# feedback.net
KiCad netlist of a schematic drawn in EAGLE
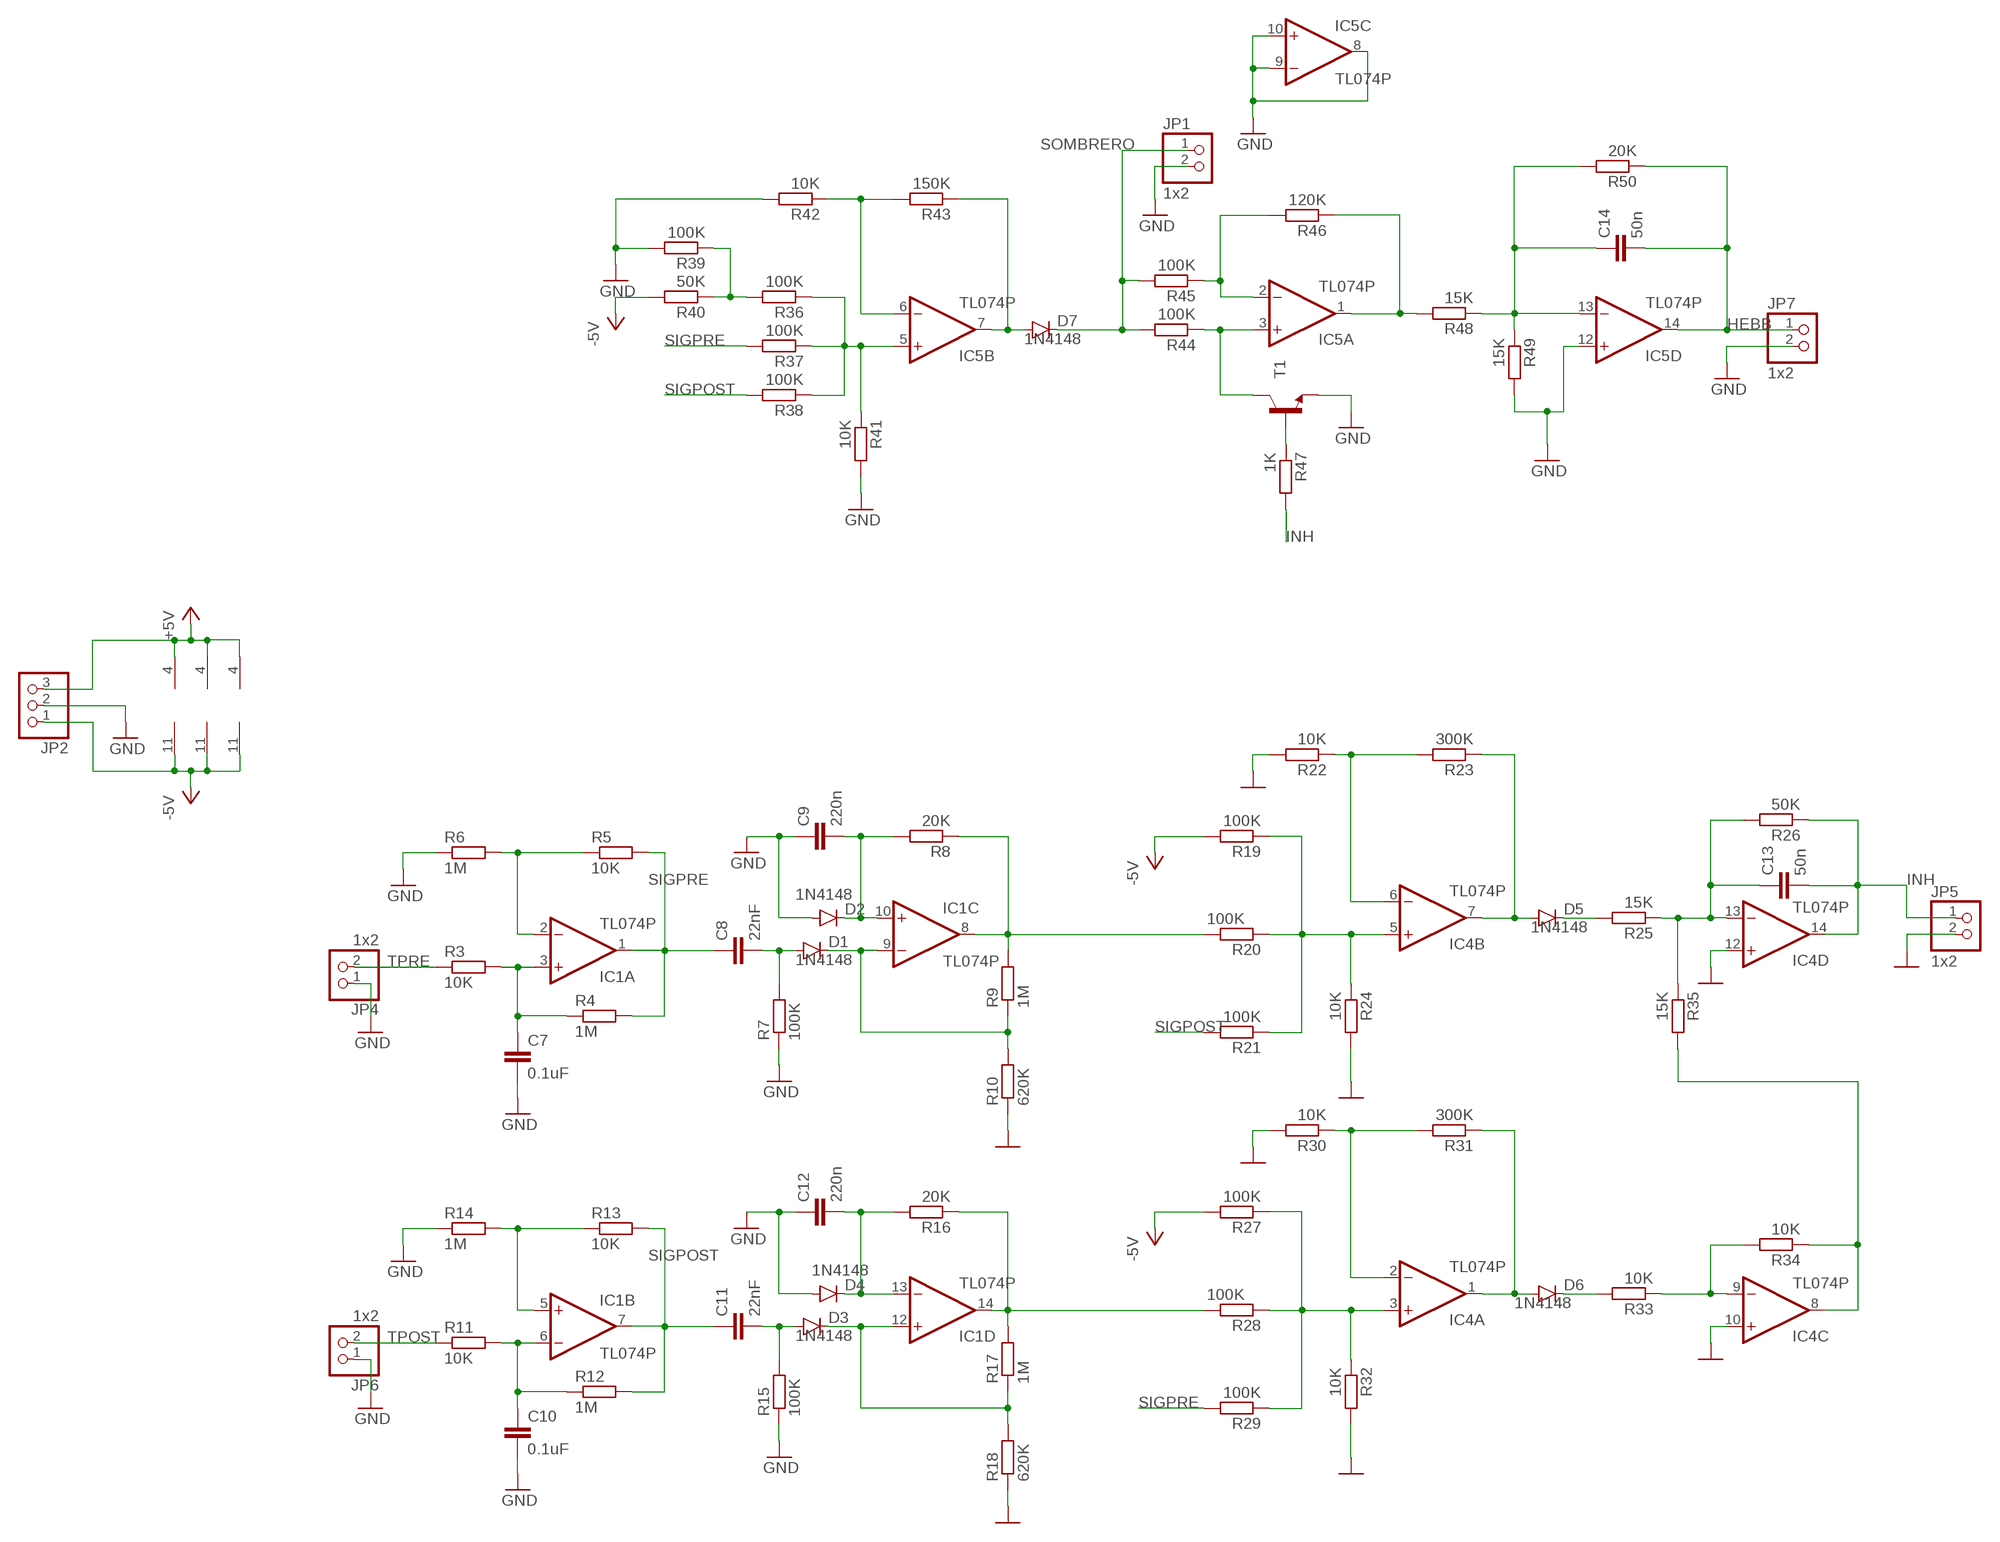
[diagram p0: schematic, sheet 1]

(export (version "E")
  (design (tool "Eeschema 10.0.6"))
  (components
    (comp (ref "C7")
      (value "0.1uF")
      (footprint "eagle-import:C050-024X044")
      (libsource (lib "eagle-import") (part "C-EU050-024X044"))
    )
    (comp (ref "C8")
      (value "22nF")
      (footprint "eagle-import:C050-024X044")
      (libsource (lib "eagle-import") (part "C-EU050-024X044"))
    )
    (comp (ref "C9")
      (value "220n")
      (footprint "eagle-import:C050-024X044")
      (libsource (lib "eagle-import") (part "C-EU050-024X044"))
    )
    (comp (ref "C10")
      (value "0.1uF")
      (footprint "eagle-import:C050-024X044")
      (libsource (lib "eagle-import") (part "C-EU050-024X044"))
    )
    (comp (ref "C11")
      (value "22nF")
      (footprint "eagle-import:C050-024X044")
      (libsource (lib "eagle-import") (part "C-EU050-024X044"))
    )
    (comp (ref "C12")
      (value "220n")
      (footprint "eagle-import:C050-024X044")
      (libsource (lib "eagle-import") (part "C-EU050-024X044"))
    )
    (comp (ref "C13")
      (value "50n")
      (footprint "eagle-import:C050-024X044")
      (libsource (lib "eagle-import") (part "C-EU050-024X044"))
    )
    (comp (ref "C14")
      (value "50n")
      (footprint "eagle-import:C050-024X044")
      (libsource (lib "eagle-import") (part "C-EU050-024X044"))
    )
    (comp (ref "D1")
      (value "1N4148")
      (footprint "eagle-import:DIODE-1N4148")
      (libsource (lib "eagle-import") (part "DIODE1N4148"))
    )
    (comp (ref "D2")
      (value "1N4148")
      (footprint "eagle-import:DIODE-1N4148")
      (libsource (lib "eagle-import") (part "DIODE1N4148"))
    )
    (comp (ref "D3")
      (value "1N4148")
      (footprint "eagle-import:DIODE-1N4148")
      (libsource (lib "eagle-import") (part "DIODE1N4148"))
    )
    (comp (ref "D4")
      (value "1N4148")
      (footprint "eagle-import:DIODE-1N4148")
      (libsource (lib "eagle-import") (part "DIODE1N4148"))
    )
    (comp (ref "D5")
      (value "1N4148")
      (footprint "eagle-import:DIODE-1N4148")
      (libsource (lib "eagle-import") (part "DIODE1N4148"))
    )
    (comp (ref "D6")
      (value "1N4148")
      (footprint "eagle-import:DIODE-1N4148")
      (libsource (lib "eagle-import") (part "DIODE1N4148"))
    )
    (comp (ref "D7")
      (value "1N4148")
      (footprint "eagle-import:DIODE-1N4148")
      (libsource (lib "eagle-import") (part "DIODE1N4148"))
    )
    (comp (ref "IC1")
      (value "TL074P")
      (footprint "eagle-import:DIL14")
      (libsource (lib "eagle-import") (part "TL074P"))
    )
    (comp (ref "IC4")
      (value "TL074P")
      (footprint "eagle-import:DIL14")
      (libsource (lib "eagle-import") (part "TL074P"))
    )
    (comp (ref "IC5")
      (value "TL074P")
      (footprint "eagle-import:DIL14")
      (libsource (lib "eagle-import") (part "TL074P"))
    )
    (comp (ref "JP1")
      (value "1x2")
      (footprint "eagle-import:1X02")
      (libsource (lib "eagle-import") (part "PINHD-1X2"))
    )
    (comp (ref "JP2")
      (value "PINHD-1X3")
      (footprint "eagle-import:1X03")
      (libsource (lib "eagle-import") (part "PINHD-1X3"))
    )
    (comp (ref "JP4")
      (value "1x2")
      (footprint "eagle-import:1X02")
      (libsource (lib "eagle-import") (part "PINHD-1X2"))
    )
    (comp (ref "JP5")
      (value "1x2")
      (footprint "eagle-import:1X02")
      (libsource (lib "eagle-import") (part "PINHD-1X2"))
    )
    (comp (ref "JP6")
      (value "1x2")
      (footprint "eagle-import:1X02")
      (libsource (lib "eagle-import") (part "PINHD-1X2"))
    )
    (comp (ref "JP7")
      (value "1x2")
      (footprint "eagle-import:1X02")
      (libsource (lib "eagle-import") (part "PINHD-1X2"))
    )
    (comp (ref "R3")
      (value "10K")
      (footprint "eagle-import:0207_10")
      (libsource (lib "eagle-import") (part "R-EU_0207/10"))
    )
    (comp (ref "R4")
      (value "1M")
      (footprint "eagle-import:0207_10")
      (libsource (lib "eagle-import") (part "R-EU_0207/10"))
    )
    (comp (ref "R5")
      (value "10K")
      (footprint "eagle-import:0207_10")
      (libsource (lib "eagle-import") (part "R-EU_0207/10"))
    )
    (comp (ref "R6")
      (value "1M")
      (footprint "eagle-import:0207_10")
      (libsource (lib "eagle-import") (part "R-EU_0207/10"))
    )
    (comp (ref "R7")
      (value "100K")
      (footprint "eagle-import:0207_10")
      (libsource (lib "eagle-import") (part "R-EU_0207/10"))
    )
    (comp (ref "R8")
      (value "20K")
      (footprint "eagle-import:0207_10")
      (libsource (lib "eagle-import") (part "R-EU_0207/10"))
    )
    (comp (ref "R9")
      (value "1M")
      (footprint "eagle-import:0207_10")
      (libsource (lib "eagle-import") (part "R-EU_0207/10"))
    )
    (comp (ref "R10")
      (value "620K")
      (footprint "eagle-import:0207_10")
      (libsource (lib "eagle-import") (part "R-EU_0207/10"))
    )
    (comp (ref "R11")
      (value "10K")
      (footprint "eagle-import:0207_10")
      (libsource (lib "eagle-import") (part "R-EU_0207/10"))
    )
    (comp (ref "R12")
      (value "1M")
      (footprint "eagle-import:0207_10")
      (libsource (lib "eagle-import") (part "R-EU_0207/10"))
    )
    (comp (ref "R13")
      (value "10K")
      (footprint "eagle-import:0207_10")
      (libsource (lib "eagle-import") (part "R-EU_0207/10"))
    )
    (comp (ref "R14")
      (value "1M")
      (footprint "eagle-import:0207_10")
      (libsource (lib "eagle-import") (part "R-EU_0207/10"))
    )
    (comp (ref "R15")
      (value "100K")
      (footprint "eagle-import:0207_10")
      (libsource (lib "eagle-import") (part "R-EU_0207/10"))
    )
    (comp (ref "R16")
      (value "20K")
      (footprint "eagle-import:0207_10")
      (libsource (lib "eagle-import") (part "R-EU_0207/10"))
    )
    (comp (ref "R17")
      (value "1M")
      (footprint "eagle-import:0207_10")
      (libsource (lib "eagle-import") (part "R-EU_0207/10"))
    )
    (comp (ref "R18")
      (value "620K")
      (footprint "eagle-import:0207_10")
      (libsource (lib "eagle-import") (part "R-EU_0207/10"))
    )
    (comp (ref "R19")
      (value "100K")
      (footprint "eagle-import:0207_10")
      (libsource (lib "eagle-import") (part "R-EU_0207/10"))
    )
    (comp (ref "R20")
      (value "100K")
      (footprint "eagle-import:0207_10")
      (libsource (lib "eagle-import") (part "R-EU_0207/10"))
    )
    (comp (ref "R21")
      (value "100K")
      (footprint "eagle-import:0207_10")
      (libsource (lib "eagle-import") (part "R-EU_0207/10"))
    )
    (comp (ref "R22")
      (value "10K")
      (footprint "eagle-import:0207_10")
      (libsource (lib "eagle-import") (part "R-EU_0207/10"))
    )
    (comp (ref "R23")
      (value "300K")
      (footprint "eagle-import:0207_10")
      (libsource (lib "eagle-import") (part "R-EU_0207/10"))
    )
    (comp (ref "R24")
      (value "10K")
      (footprint "eagle-import:0207_10")
      (libsource (lib "eagle-import") (part "R-EU_0207/10"))
    )
    (comp (ref "R25")
      (value "15K")
      (footprint "eagle-import:0207_10")
      (libsource (lib "eagle-import") (part "R-EU_0207/10"))
    )
    (comp (ref "R26")
      (value "50K")
      (footprint "eagle-import:0207_10")
      (libsource (lib "eagle-import") (part "R-EU_0207/10"))
    )
    (comp (ref "R27")
      (value "100K")
      (footprint "eagle-import:0207_10")
      (libsource (lib "eagle-import") (part "R-EU_0207/10"))
    )
    (comp (ref "R28")
      (value "100K")
      (footprint "eagle-import:0207_10")
      (libsource (lib "eagle-import") (part "R-EU_0207/10"))
    )
    (comp (ref "R29")
      (value "100K")
      (footprint "eagle-import:0207_10")
      (libsource (lib "eagle-import") (part "R-EU_0207/10"))
    )
    (comp (ref "R30")
      (value "10K")
      (footprint "eagle-import:0207_10")
      (libsource (lib "eagle-import") (part "R-EU_0207/10"))
    )
    (comp (ref "R31")
      (value "300K")
      (footprint "eagle-import:0207_10")
      (libsource (lib "eagle-import") (part "R-EU_0207/10"))
    )
    (comp (ref "R32")
      (value "10K")
      (footprint "eagle-import:0207_10")
      (libsource (lib "eagle-import") (part "R-EU_0207/10"))
    )
    (comp (ref "R33")
      (value "10K")
      (footprint "eagle-import:0207_10")
      (libsource (lib "eagle-import") (part "R-EU_0207/10"))
    )
    (comp (ref "R34")
      (value "10K")
      (footprint "eagle-import:0207_10")
      (libsource (lib "eagle-import") (part "R-EU_0207/10"))
    )
    (comp (ref "R35")
      (value "15K")
      (footprint "eagle-import:0207_10")
      (libsource (lib "eagle-import") (part "R-EU_0207/10"))
    )
    (comp (ref "R36")
      (value "100K")
      (footprint "eagle-import:0207_10")
      (libsource (lib "eagle-import") (part "R-EU_0207/10"))
    )
    (comp (ref "R37")
      (value "100K")
      (footprint "eagle-import:0207_10")
      (libsource (lib "eagle-import") (part "R-EU_0207/10"))
    )
    (comp (ref "R38")
      (value "100K")
      (footprint "eagle-import:0207_10")
      (libsource (lib "eagle-import") (part "R-EU_0207/10"))
    )
    (comp (ref "R39")
      (value "100K")
      (footprint "eagle-import:0207_10")
      (fields (field (name "SPICEPREFIX") "R"))
      (libsource (lib "eagle-import") (part "R-EU_0207/10"))
    )
    (comp (ref "R40")
      (value "50K")
      (footprint "eagle-import:0207_10")
      (libsource (lib "eagle-import") (part "R-EU_0207/10"))
    )
    (comp (ref "R41")
      (value "10K")
      (footprint "eagle-import:0207_10")
      (libsource (lib "eagle-import") (part "R-EU_0207/10"))
    )
    (comp (ref "R42")
      (value "10K")
      (footprint "eagle-import:0207_10")
      (fields (field (name "SPICEPREFIX") "R"))
      (libsource (lib "eagle-import") (part "R-EU_0207/10"))
    )
    (comp (ref "R43")
      (value "150K")
      (footprint "eagle-import:0207_10")
      (fields (field (name "SPICEPREFIX") "R"))
      (libsource (lib "eagle-import") (part "R-EU_0207/10"))
    )
    (comp (ref "R44")
      (value "100K")
      (footprint "eagle-import:0207_10")
      (libsource (lib "eagle-import") (part "R-EU_0207/10"))
    )
    (comp (ref "R45")
      (value "100K")
      (footprint "eagle-import:0207_10")
      (libsource (lib "eagle-import") (part "R-EU_0207/10"))
    )
    (comp (ref "R46")
      (value "120K")
      (footprint "eagle-import:0207_10")
      (libsource (lib "eagle-import") (part "R-EU_0207/10"))
    )
    (comp (ref "R47")
      (value "1K")
      (footprint "eagle-import:0207_10")
      (libsource (lib "eagle-import") (part "R-EU_0207/10"))
    )
    (comp (ref "R48")
      (value "15K")
      (footprint "eagle-import:0207_10")
      (libsource (lib "eagle-import") (part "R-EU_0207/10"))
    )
    (comp (ref "R49")
      (value "15K")
      (footprint "eagle-import:0207_10")
      (libsource (lib "eagle-import") (part "R-EU_0207/10"))
    )
    (comp (ref "R50")
      (value "20K")
      (footprint "eagle-import:0207_10")
      (libsource (lib "eagle-import") (part "R-EU_0207/10"))
    )
    (comp (ref "T1")
      (value "BC337-25-NPN-TO92-CBE")
      (footprint "eagle-import:TO92-CBE")
      (libsource (lib "eagle-import") (part "-NPN-TO92-CBEBC337-25"))
    )
  )
  (nets
    (net (code "1") (name "+5V") (class "Default")
      (node (ref "IC1") (pin "4") (pinfunction "V+_4") (pintype "power_in"))
      (node (ref "IC4") (pin "4") (pinfunction "V+_4") (pintype "power_in"))
      (node (ref "IC5") (pin "4") (pinfunction "V+_4") (pintype "power_in"))
      (node (ref "JP2") (pin "3") (pinfunction "3_3") (pintype "passive"))
    )
    (net (code "2") (name "-5V") (class "Default")
      (node (ref "IC1") (pin "11") (pinfunction "V-_11") (pintype "power_in"))
      (node (ref "IC4") (pin "11") (pinfunction "V-_11") (pintype "power_in"))
      (node (ref "IC5") (pin "11") (pinfunction "V-_11") (pintype "power_in"))
      (node (ref "JP2") (pin "1") (pinfunction "1_1") (pintype "passive"))
      (node (ref "R19") (pin "2") (pinfunction "2_2") (pintype "passive"))
      (node (ref "R27") (pin "2") (pinfunction "2_2") (pintype "passive"))
      (node (ref "R40") (pin "2") (pinfunction "2_2") (pintype "passive"))
    )
    (net (code "3") (name "/HEBB") (class "Default")
      (node (ref "C14") (pin "2") (pinfunction "2_2") (pintype "passive"))
      (node (ref "IC5") (pin "14") (pinfunction "OUT_14") (pintype "output"))
      (node (ref "JP7") (pin "1") (pinfunction "1_1") (pintype "passive"))
      (node (ref "R50") (pin "1") (pinfunction "1_1") (pintype "passive"))
    )
    (net (code "4") (name "/INH") (class "Default")
      (node (ref "C13") (pin "2") (pinfunction "2_2") (pintype "passive"))
      (node (ref "IC4") (pin "14") (pinfunction "OUT_14") (pintype "output"))
      (node (ref "JP5") (pin "1") (pinfunction "1_1") (pintype "passive"))
      (node (ref "R26") (pin "1") (pinfunction "1_1") (pintype "passive"))
      (node (ref "R47") (pin "2") (pinfunction "2_2") (pintype "passive"))
    )
    (net (code "5") (name "/SIGPOST") (class "Default")
      (node (ref "C11") (pin "1") (pinfunction "1_1") (pintype "passive"))
      (node (ref "IC1") (pin "7") (pinfunction "OUT_7") (pintype "output"))
      (node (ref "R12") (pin "2") (pinfunction "2_2") (pintype "passive"))
      (node (ref "R13") (pin "2") (pinfunction "2_2") (pintype "passive"))
      (node (ref "R21") (pin "2") (pinfunction "2_2") (pintype "passive"))
      (node (ref "R38") (pin "2") (pinfunction "2_2") (pintype "passive"))
    )
    (net (code "6") (name "/SIGPRE") (class "Default")
      (node (ref "C8") (pin "1") (pinfunction "1_1") (pintype "passive"))
      (node (ref "IC1") (pin "1") (pinfunction "OUT_1") (pintype "output"))
      (node (ref "R29") (pin "2") (pinfunction "2_2") (pintype "passive"))
      (node (ref "R37") (pin "2") (pinfunction "2_2") (pintype "passive"))
      (node (ref "R4") (pin "2") (pinfunction "2_2") (pintype "passive"))
      (node (ref "R5") (pin "2") (pinfunction "2_2") (pintype "passive"))
    )
    (net (code "7") (name "/SOMBRERO") (class "Default")
      (node (ref "D7") (pin "C") (pinfunction "C_C") (pintype "passive"))
      (node (ref "JP1") (pin "1") (pinfunction "1_1") (pintype "passive"))
      (node (ref "R44") (pin "2") (pinfunction "2_2") (pintype "passive"))
      (node (ref "R45") (pin "2") (pinfunction "2_2") (pintype "passive"))
    )
    (net (code "8") (name "/TPOST") (class "Default")
      (node (ref "JP6") (pin "2") (pinfunction "2_2") (pintype "passive"))
      (node (ref "R11") (pin "1") (pinfunction "1_1") (pintype "passive"))
    )
    (net (code "9") (name "/TPRE") (class "Default")
      (node (ref "JP4") (pin "2") (pinfunction "2_2") (pintype "passive"))
      (node (ref "R3") (pin "1") (pinfunction "1_1") (pintype "passive"))
    )
    (net (code "10") (name "GND") (class "Default")
      (node (ref "C10") (pin "2") (pinfunction "2_2") (pintype "passive"))
      (node (ref "C12") (pin "1") (pinfunction "1_1") (pintype "passive"))
      (node (ref "C7") (pin "2") (pinfunction "2_2") (pintype "passive"))
      (node (ref "C9") (pin "1") (pinfunction "1_1") (pintype "passive"))
      (node (ref "D2") (pin "A") (pinfunction "A_A") (pintype "passive"))
      (node (ref "D4") (pin "A") (pinfunction "A_A") (pintype "passive"))
      (node (ref "IC4") (pin "10") (pinfunction "+IN_10") (pintype "input"))
      (node (ref "IC4") (pin "12") (pinfunction "+IN_12") (pintype "input"))
      (node (ref "IC5") (pin "10") (pinfunction "+IN_10") (pintype "input"))
      (node (ref "IC5") (pin "12") (pinfunction "+IN_12") (pintype "input"))
      (node (ref "IC5") (pin "8") (pinfunction "OUT_8") (pintype "output"))
      (node (ref "IC5") (pin "9") (pinfunction "-IN_9") (pintype "input"))
      (node (ref "JP1") (pin "2") (pinfunction "2_2") (pintype "passive"))
      (node (ref "JP2") (pin "2") (pinfunction "2_2") (pintype "passive"))
      (node (ref "JP4") (pin "1") (pinfunction "1_1") (pintype "passive"))
      (node (ref "JP5") (pin "2") (pinfunction "2_2") (pintype "passive"))
      (node (ref "JP6") (pin "1") (pinfunction "1_1") (pintype "passive"))
      (node (ref "JP7") (pin "2") (pinfunction "2_2") (pintype "passive"))
      (node (ref "R10") (pin "1") (pinfunction "1_1") (pintype "passive"))
      (node (ref "R14") (pin "1") (pinfunction "1_1") (pintype "passive"))
      (node (ref "R15") (pin "1") (pinfunction "1_1") (pintype "passive"))
      (node (ref "R18") (pin "1") (pinfunction "1_1") (pintype "passive"))
      (node (ref "R22") (pin "2") (pinfunction "2_2") (pintype "passive"))
      (node (ref "R24") (pin "2") (pinfunction "2_2") (pintype "passive"))
      (node (ref "R30") (pin "2") (pinfunction "2_2") (pintype "passive"))
      (node (ref "R32") (pin "2") (pinfunction "2_2") (pintype "passive"))
      (node (ref "R39") (pin "2") (pinfunction "2_2") (pintype "passive"))
      (node (ref "R41") (pin "2") (pinfunction "2_2") (pintype "passive"))
      (node (ref "R42") (pin "2") (pinfunction "2_2") (pintype "passive"))
      (node (ref "R49") (pin "2") (pinfunction "2_2") (pintype "passive"))
      (node (ref "R6") (pin "1") (pinfunction "1_1") (pintype "passive"))
      (node (ref "R7") (pin "1") (pinfunction "1_1") (pintype "passive"))
      (node (ref "T1") (pin "E") (pinfunction "E_E") (pintype "passive"))
    )
    (net (code "11") (name "Net-(C8-Pad2)") (class "Default")
      (node (ref "C8") (pin "2") (pinfunction "2_2") (pintype "passive"))
      (node (ref "D1") (pin "A") (pinfunction "A_A") (pintype "passive"))
      (node (ref "R7") (pin "2") (pinfunction "2_2") (pintype "passive"))
    )
    (net (code "12") (name "Net-(C11-Pad2)") (class "Default")
      (node (ref "C11") (pin "2") (pinfunction "2_2") (pintype "passive"))
      (node (ref "D3") (pin "A") (pinfunction "A_A") (pintype "passive"))
      (node (ref "R15") (pin "2") (pinfunction "2_2") (pintype "passive"))
    )
    (net (code "13") (name "Net-(D5-PadC)") (class "Default")
      (node (ref "D5") (pin "C") (pinfunction "C_C") (pintype "passive"))
      (node (ref "R25") (pin "2") (pinfunction "2_2") (pintype "passive"))
    )
    (net (code "14") (name "Net-(D6-PadC)") (class "Default")
      (node (ref "D6") (pin "C") (pinfunction "C_C") (pintype "passive"))
      (node (ref "R33") (pin "2") (pinfunction "2_2") (pintype "passive"))
    )
    (net (code "15") (name "Net-(IC1A-+IN)") (class "Default")
      (node (ref "C7") (pin "1") (pinfunction "1_1") (pintype "passive"))
      (node (ref "IC1") (pin "3") (pinfunction "+IN_3") (pintype "input"))
      (node (ref "R3") (pin "2") (pinfunction "2_2") (pintype "passive"))
      (node (ref "R4") (pin "1") (pinfunction "1_1") (pintype "passive"))
    )
    (net (code "16") (name "Net-(IC1A--IN)") (class "Default")
      (node (ref "IC1") (pin "2") (pinfunction "-IN_2") (pintype "input"))
      (node (ref "R5") (pin "1") (pinfunction "1_1") (pintype "passive"))
      (node (ref "R6") (pin "2") (pinfunction "2_2") (pintype "passive"))
    )
    (net (code "17") (name "Net-(IC1B-+IN)") (class "Default")
      (node (ref "IC1") (pin "5") (pinfunction "+IN_5") (pintype "input"))
      (node (ref "R13") (pin "1") (pinfunction "1_1") (pintype "passive"))
      (node (ref "R14") (pin "2") (pinfunction "2_2") (pintype "passive"))
    )
    (net (code "18") (name "Net-(IC1B--IN)") (class "Default")
      (node (ref "C10") (pin "1") (pinfunction "1_1") (pintype "passive"))
      (node (ref "IC1") (pin "6") (pinfunction "-IN_6") (pintype "input"))
      (node (ref "R11") (pin "2") (pinfunction "2_2") (pintype "passive"))
      (node (ref "R12") (pin "1") (pinfunction "1_1") (pintype "passive"))
    )
    (net (code "19") (name "Net-(IC1C-+IN)") (class "Default")
      (node (ref "C9") (pin "2") (pinfunction "2_2") (pintype "passive"))
      (node (ref "D2") (pin "C") (pinfunction "C_C") (pintype "passive"))
      (node (ref "IC1") (pin "10") (pinfunction "+IN_10") (pintype "input"))
      (node (ref "R8") (pin "2") (pinfunction "2_2") (pintype "passive"))
    )
    (net (code "20") (name "Net-(IC1C--IN)") (class "Default")
      (node (ref "D1") (pin "C") (pinfunction "C_C") (pintype "passive"))
      (node (ref "IC1") (pin "9") (pinfunction "-IN_9") (pintype "input"))
      (node (ref "R10") (pin "2") (pinfunction "2_2") (pintype "passive"))
      (node (ref "R9") (pin "1") (pinfunction "1_1") (pintype "passive"))
    )
    (net (code "21") (name "Net-(IC1C-OUT)") (class "Default")
      (node (ref "IC1") (pin "8") (pinfunction "OUT_8") (pintype "output"))
      (node (ref "R20") (pin "2") (pinfunction "2_2") (pintype "passive"))
      (node (ref "R8") (pin "1") (pinfunction "1_1") (pintype "passive"))
      (node (ref "R9") (pin "2") (pinfunction "2_2") (pintype "passive"))
    )
    (net (code "22") (name "Net-(IC1D-+IN)") (class "Default")
      (node (ref "D3") (pin "C") (pinfunction "C_C") (pintype "passive"))
      (node (ref "IC1") (pin "12") (pinfunction "+IN_12") (pintype "input"))
      (node (ref "R17") (pin "1") (pinfunction "1_1") (pintype "passive"))
      (node (ref "R18") (pin "2") (pinfunction "2_2") (pintype "passive"))
    )
    (net (code "23") (name "Net-(IC1D--IN)") (class "Default")
      (node (ref "C12") (pin "2") (pinfunction "2_2") (pintype "passive"))
      (node (ref "D4") (pin "C") (pinfunction "C_C") (pintype "passive"))
      (node (ref "IC1") (pin "13") (pinfunction "-IN_13") (pintype "input"))
      (node (ref "R16") (pin "2") (pinfunction "2_2") (pintype "passive"))
    )
    (net (code "24") (name "Net-(IC1D-OUT)") (class "Default")
      (node (ref "IC1") (pin "14") (pinfunction "OUT_14") (pintype "output"))
      (node (ref "R16") (pin "1") (pinfunction "1_1") (pintype "passive"))
      (node (ref "R17") (pin "2") (pinfunction "2_2") (pintype "passive"))
      (node (ref "R28") (pin "2") (pinfunction "2_2") (pintype "passive"))
    )
    (net (code "25") (name "Net-(IC4A-+IN)") (class "Default")
      (node (ref "IC4") (pin "3") (pinfunction "+IN_3") (pintype "input"))
      (node (ref "R27") (pin "1") (pinfunction "1_1") (pintype "passive"))
      (node (ref "R28") (pin "1") (pinfunction "1_1") (pintype "passive"))
      (node (ref "R29") (pin "1") (pinfunction "1_1") (pintype "passive"))
      (node (ref "R32") (pin "1") (pinfunction "1_1") (pintype "passive"))
    )
    (net (code "26") (name "Net-(IC4A--IN)") (class "Default")
      (node (ref "IC4") (pin "2") (pinfunction "-IN_2") (pintype "input"))
      (node (ref "R30") (pin "1") (pinfunction "1_1") (pintype "passive"))
      (node (ref "R31") (pin "2") (pinfunction "2_2") (pintype "passive"))
    )
    (net (code "27") (name "Net-(IC4A-OUT)") (class "Default")
      (node (ref "D6") (pin "A") (pinfunction "A_A") (pintype "passive"))
      (node (ref "IC4") (pin "1") (pinfunction "OUT_1") (pintype "output"))
      (node (ref "R31") (pin "1") (pinfunction "1_1") (pintype "passive"))
    )
    (net (code "28") (name "Net-(IC4B-+IN)") (class "Default")
      (node (ref "IC4") (pin "5") (pinfunction "+IN_5") (pintype "input"))
      (node (ref "R19") (pin "1") (pinfunction "1_1") (pintype "passive"))
      (node (ref "R20") (pin "1") (pinfunction "1_1") (pintype "passive"))
      (node (ref "R21") (pin "1") (pinfunction "1_1") (pintype "passive"))
      (node (ref "R24") (pin "1") (pinfunction "1_1") (pintype "passive"))
    )
    (net (code "29") (name "Net-(IC4B--IN)") (class "Default")
      (node (ref "IC4") (pin "6") (pinfunction "-IN_6") (pintype "input"))
      (node (ref "R22") (pin "1") (pinfunction "1_1") (pintype "passive"))
      (node (ref "R23") (pin "2") (pinfunction "2_2") (pintype "passive"))
    )
    (net (code "30") (name "Net-(IC4B-OUT)") (class "Default")
      (node (ref "D5") (pin "A") (pinfunction "A_A") (pintype "passive"))
      (node (ref "IC4") (pin "7") (pinfunction "OUT_7") (pintype "output"))
      (node (ref "R23") (pin "1") (pinfunction "1_1") (pintype "passive"))
    )
    (net (code "31") (name "Net-(IC4C--IN)") (class "Default")
      (node (ref "IC4") (pin "9") (pinfunction "-IN_9") (pintype "input"))
      (node (ref "R33") (pin "1") (pinfunction "1_1") (pintype "passive"))
      (node (ref "R34") (pin "2") (pinfunction "2_2") (pintype "passive"))
    )
    (net (code "32") (name "Net-(IC4C-OUT)") (class "Default")
      (node (ref "IC4") (pin "8") (pinfunction "OUT_8") (pintype "output"))
      (node (ref "R34") (pin "1") (pinfunction "1_1") (pintype "passive"))
      (node (ref "R35") (pin "2") (pinfunction "2_2") (pintype "passive"))
    )
    (net (code "33") (name "Net-(IC4D--IN)") (class "Default")
      (node (ref "C13") (pin "1") (pinfunction "1_1") (pintype "passive"))
      (node (ref "IC4") (pin "13") (pinfunction "-IN_13") (pintype "input"))
      (node (ref "R25") (pin "1") (pinfunction "1_1") (pintype "passive"))
      (node (ref "R26") (pin "2") (pinfunction "2_2") (pintype "passive"))
      (node (ref "R35") (pin "1") (pinfunction "1_1") (pintype "passive"))
    )
    (net (code "34") (name "Net-(IC5A-+IN)") (class "Default")
      (node (ref "IC5") (pin "3") (pinfunction "+IN_3") (pintype "input"))
      (node (ref "R44") (pin "1") (pinfunction "1_1") (pintype "passive"))
      (node (ref "T1") (pin "C") (pinfunction "C_C") (pintype "passive"))
    )
    (net (code "35") (name "Net-(IC5A--IN)") (class "Default")
      (node (ref "IC5") (pin "2") (pinfunction "-IN_2") (pintype "input"))
      (node (ref "R45") (pin "1") (pinfunction "1_1") (pintype "passive"))
      (node (ref "R46") (pin "2") (pinfunction "2_2") (pintype "passive"))
    )
    (net (code "36") (name "Net-(IC5A-OUT)") (class "Default")
      (node (ref "IC5") (pin "1") (pinfunction "OUT_1") (pintype "output"))
      (node (ref "R46") (pin "1") (pinfunction "1_1") (pintype "passive"))
      (node (ref "R48") (pin "2") (pinfunction "2_2") (pintype "passive"))
    )
    (net (code "37") (name "Net-(IC5B-+IN)") (class "Default")
      (node (ref "IC5") (pin "5") (pinfunction "+IN_5") (pintype "input"))
      (node (ref "R36") (pin "1") (pinfunction "1_1") (pintype "passive"))
      (node (ref "R37") (pin "1") (pinfunction "1_1") (pintype "passive"))
      (node (ref "R38") (pin "1") (pinfunction "1_1") (pintype "passive"))
      (node (ref "R41") (pin "1") (pinfunction "1_1") (pintype "passive"))
    )
    (net (code "38") (name "Net-(IC5B--IN)") (class "Default")
      (node (ref "IC5") (pin "6") (pinfunction "-IN_6") (pintype "input"))
      (node (ref "R42") (pin "1") (pinfunction "1_1") (pintype "passive"))
      (node (ref "R43") (pin "2") (pinfunction "2_2") (pintype "passive"))
    )
    (net (code "39") (name "Net-(IC5B-OUT)") (class "Default")
      (node (ref "D7") (pin "A") (pinfunction "A_A") (pintype "passive"))
      (node (ref "IC5") (pin "7") (pinfunction "OUT_7") (pintype "output"))
      (node (ref "R43") (pin "1") (pinfunction "1_1") (pintype "passive"))
    )
    (net (code "40") (name "Net-(IC5D--IN)") (class "Default")
      (node (ref "C14") (pin "1") (pinfunction "1_1") (pintype "passive"))
      (node (ref "IC5") (pin "13") (pinfunction "-IN_13") (pintype "input"))
      (node (ref "R48") (pin "1") (pinfunction "1_1") (pintype "passive"))
      (node (ref "R49") (pin "1") (pinfunction "1_1") (pintype "passive"))
      (node (ref "R50") (pin "2") (pinfunction "2_2") (pintype "passive"))
    )
    (net (code "41") (name "Net-(R36-Pad2)") (class "Default")
      (node (ref "R36") (pin "2") (pinfunction "2_2") (pintype "passive"))
      (node (ref "R39") (pin "1") (pinfunction "1_1") (pintype "passive"))
      (node (ref "R40") (pin "1") (pinfunction "1_1") (pintype "passive"))
    )
    (net (code "42") (name "Net-(R47-Pad1)") (class "Default")
      (node (ref "R47") (pin "1") (pinfunction "1_1") (pintype "passive"))
      (node (ref "T1") (pin "B") (pinfunction "B_B") (pintype "passive"))
    )
  )
)
